# Spring12_6_daughterboard.net
KiCad netlist of a schematic drawn in EAGLE
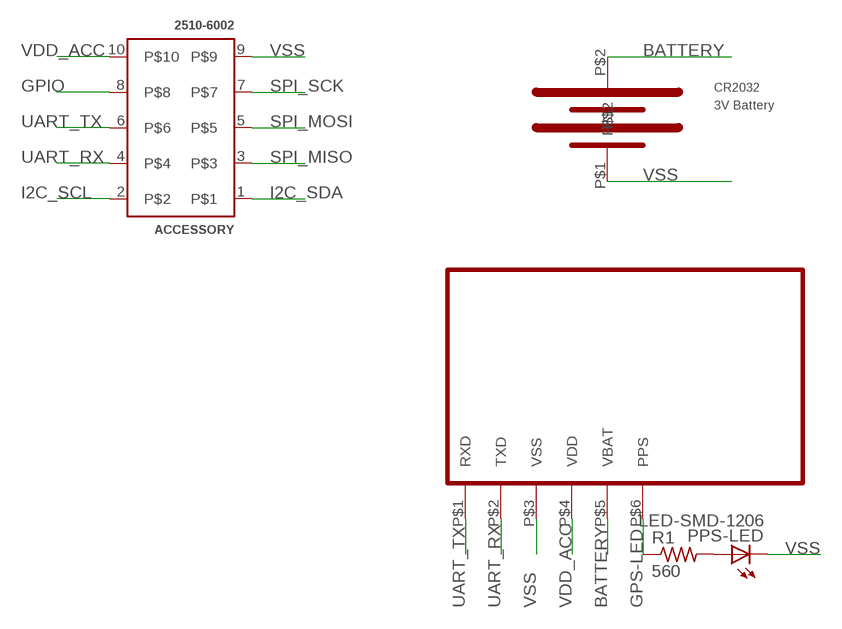
[diagram p0: schematic, sheet 1]

(export (version "E")
  (design (tool "Eeschema 10.0.6"))
  (components
    (comp (ref "ACCESSORY")
      (value "2510-6002")
      (footprint "eagle-import:2510-6002")
      (libsource (lib "eagle-import") (part "2510-6002"))
    )
    (comp (ref "PPS-LED")
      (value "LED-SMD-1206")
      (footprint "eagle-import:LED1206")
      (libsource (lib "eagle-import") (part "LED-SMD-1206"))
    )
    (comp (ref "R1")
      (value "560")
      (footprint "eagle-import:R1206")
      (libsource (lib "eagle-import") (part "R-US_R1206"))
    )
    (comp (ref "U$1")
      (value "796136-1-CR2302_HOLDER")
      (footprint "eagle-import:796136-1-CR2032_HOLDER")
      (libsource (lib "eagle-import") (part "796136-1-CR2302_HOLDER"))
    )
    (comp (ref "U$3")
      (value "GPS-UP501")
      (footprint "eagle-import:GPS-UP501")
      (libsource (lib "eagle-import") (part "GPS-UP501"))
    )
  )
  (nets
    (net (code "1") (name "/BATTERY") (class "Default")
      (node (ref "U$1") (pin "P$2") (pinfunction "P$1_P$2") (pintype "power_in"))
      (node (ref "U$3") (pin "P$5") (pinfunction "VBAT_P$5") (pintype "bidirectional"))
    )
    (net (code "2") (name "/GPIO") (class "Default")
      (node (ref "ACCESSORY") (pin "8") (pinfunction "P$8_8") (pintype "passive"))
    )
    (net (code "3") (name "/GPS-LED") (class "Default")
      (node (ref "R1") (pin "1") (pinfunction "1_1") (pintype "passive"))
      (node (ref "U$3") (pin "P$6") (pinfunction "PPS_P$6") (pintype "bidirectional"))
    )
    (net (code "4") (name "/I2C_SCL") (class "Default")
      (node (ref "ACCESSORY") (pin "2") (pinfunction "P$2_2") (pintype "passive"))
    )
    (net (code "5") (name "/I2C_SDA") (class "Default")
      (node (ref "ACCESSORY") (pin "1") (pinfunction "P$1_1") (pintype "passive"))
    )
    (net (code "6") (name "/SPI_MISO") (class "Default")
      (node (ref "ACCESSORY") (pin "3") (pinfunction "P$3_3") (pintype "passive"))
    )
    (net (code "7") (name "/SPI_MOSI") (class "Default")
      (node (ref "ACCESSORY") (pin "5") (pinfunction "P$5_5") (pintype "passive"))
    )
    (net (code "8") (name "/SPI_SCK") (class "Default")
      (node (ref "ACCESSORY") (pin "7") (pinfunction "P$7_7") (pintype "passive"))
    )
    (net (code "9") (name "/UART_RX") (class "Default")
      (node (ref "ACCESSORY") (pin "4") (pinfunction "P$4_4") (pintype "passive"))
      (node (ref "U$3") (pin "P$2") (pinfunction "TXD_P$2") (pintype "bidirectional"))
    )
    (net (code "10") (name "/UART_TX") (class "Default")
      (node (ref "ACCESSORY") (pin "6") (pinfunction "P$6_6") (pintype "passive"))
      (node (ref "U$3") (pin "P$1") (pinfunction "RXD_P$1") (pintype "bidirectional"))
    )
    (net (code "11") (name "/VDD_ACC") (class "Default")
      (node (ref "ACCESSORY") (pin "10") (pinfunction "P$10_10") (pintype "passive"))
      (node (ref "U$3") (pin "P$4") (pinfunction "VDD_P$4") (pintype "bidirectional"))
    )
    (net (code "12") (name "/VSS") (class "Default")
      (node (ref "ACCESSORY") (pin "9") (pinfunction "P$9_9") (pintype "passive"))
      (node (ref "PPS-LED") (pin "C") (pinfunction "C_C") (pintype "passive"))
      (node (ref "U$1") (pin "P$1") (pinfunction "P$2_P$1") (pintype "power_in"))
      (node (ref "U$3") (pin "P$3") (pinfunction "VSS_P$3") (pintype "bidirectional"))
    )
    (net (code "13") (name "Net-(PPS-LED-PadA)") (class "Default")
      (node (ref "PPS-LED") (pin "A") (pinfunction "A_A") (pintype "passive"))
      (node (ref "R1") (pin "2") (pinfunction "2_2") (pintype "passive"))
    )
  )
)
